# IOIO_Pump.net
KiCad netlist of a schematic drawn in EAGLE
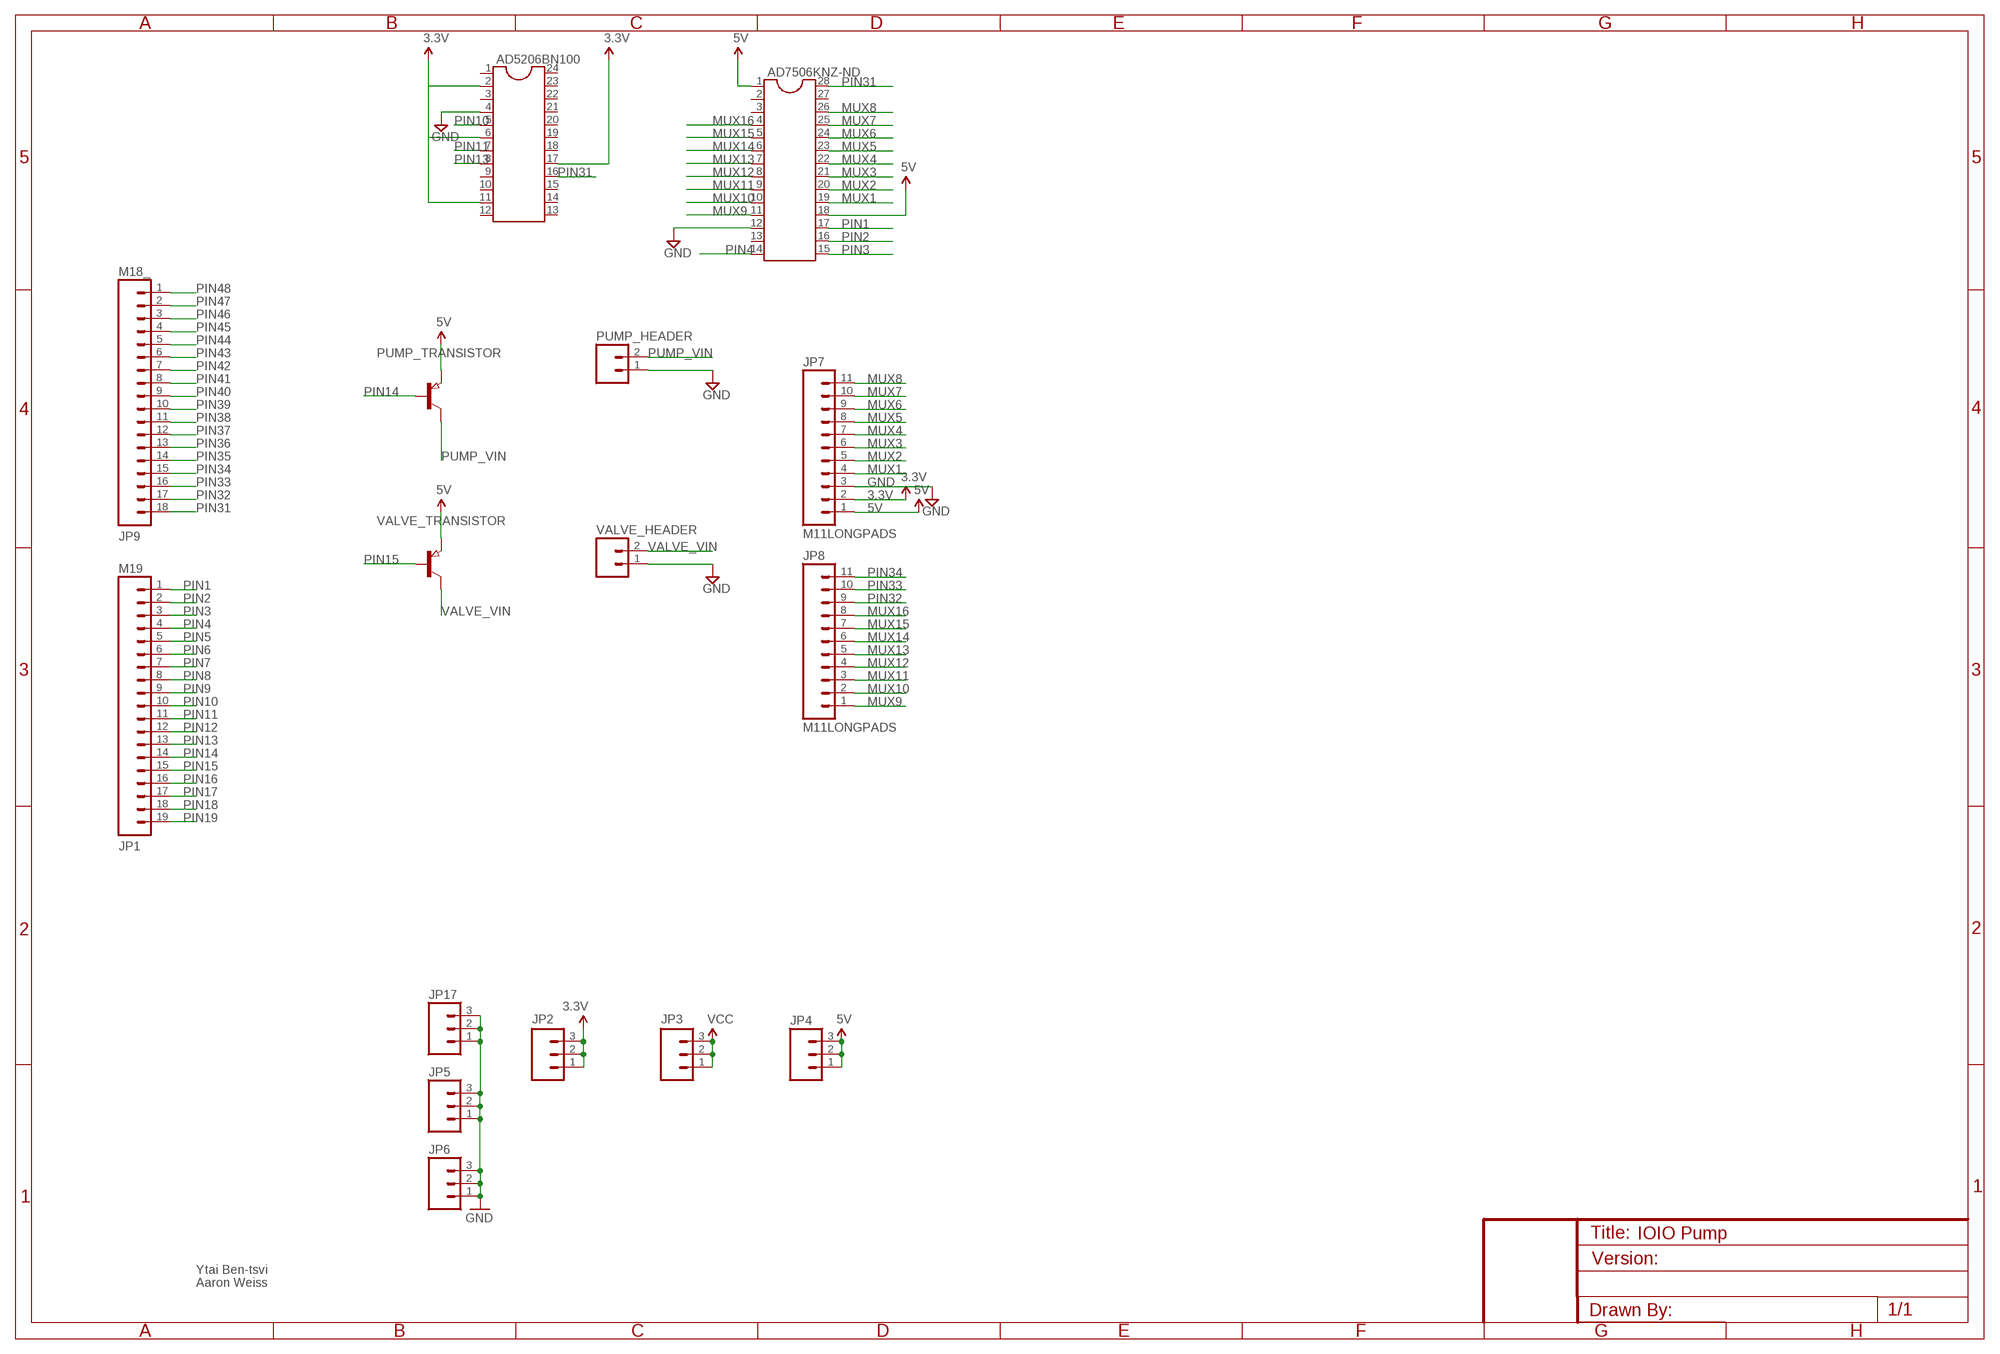
[diagram p0: schematic, sheet 1]

(export (version "E")
  (design (tool "Eeschema 10.0.6"))
  (components
    (comp (ref "AD5206BN100")
      (value "DIL24-3")
      (footprint "eagle-import:DIL24-3")
      (libsource (lib "eagle-import") (part "DIL24-3"))
    )
    (comp (ref "AD7506KNZ-ND")
      (value "DIL28")
      (footprint "eagle-import:DIL28-6")
      (libsource (lib "eagle-import") (part "DIL28"))
    )
    (comp (ref "JP1")
      (value "M19")
      (footprint "eagle-import:1X19")
      (libsource (lib "eagle-import") (part "M19"))
    )
    (comp (ref "JP2")
      (value "M03PTH")
      (footprint "eagle-import:1X03")
      (libsource (lib "eagle-import") (part "M03PTH"))
    )
    (comp (ref "JP3")
      (value "M03PTH")
      (footprint "eagle-import:1X03")
      (libsource (lib "eagle-import") (part "M03PTH"))
    )
    (comp (ref "JP4")
      (value "M03PTH")
      (footprint "eagle-import:1X03")
      (libsource (lib "eagle-import") (part "M03PTH"))
    )
    (comp (ref "JP5")
      (value "M03PTH")
      (footprint "eagle-import:1X03")
      (libsource (lib "eagle-import") (part "M03PTH"))
    )
    (comp (ref "JP6")
      (value "M03PTH")
      (footprint "eagle-import:1X03")
      (libsource (lib "eagle-import") (part "M03PTH"))
    )
    (comp (ref "JP7")
      (value "M11LONGPADS")
      (footprint "eagle-import:1X11_LONGPADS")
      (libsource (lib "eagle-import") (part "M11LONGPADS"))
    )
    (comp (ref "JP8")
      (value "M11LONGPADS")
      (footprint "eagle-import:1X11_LONGPADS")
      (libsource (lib "eagle-import") (part "M11LONGPADS"))
    )
    (comp (ref "JP9")
      (value "M18_")
      (footprint "eagle-import:1X18")
      (libsource (lib "eagle-import") (part "M18_"))
    )
    (comp (ref "JP17")
      (value "M03PTH")
      (footprint "eagle-import:1X03")
      (libsource (lib "eagle-import") (part "M03PTH"))
    )
    (comp (ref "PUMP_HEADER")
      (value "M02PTH")
      (footprint "eagle-import:1X02")
      (libsource (lib "eagle-import") (part "M02PTH"))
    )
    (comp (ref "PUMP_TRANSISTOR")
      (value "PNP-TRANSISTOR_SOT23")
      (footprint "eagle-import:SOT23")
      (libsource (lib "eagle-import") (part "PNP-TRANSISTOR_SOT23"))
    )
    (comp (ref "VALVE_HEADER")
      (value "M02PTH")
      (footprint "eagle-import:1X02")
      (libsource (lib "eagle-import") (part "M02PTH"))
    )
    (comp (ref "VALVE_TRANSISTOR")
      (value "PNP-TRANSISTOR_SOT23")
      (footprint "eagle-import:SOT23")
      (libsource (lib "eagle-import") (part "PNP-TRANSISTOR_SOT23"))
    )
  )
  (nets
    (net (code "1") (name "/MUX1") (class "Default")
      (node (ref "AD7506KNZ-ND") (pin "19") (pinfunction "19_19") (pintype "passive"))
      (node (ref "JP7") (pin "4") (pinfunction "4_4") (pintype "passive"))
    )
    (net (code "2") (name "/MUX2") (class "Default")
      (node (ref "AD7506KNZ-ND") (pin "20") (pinfunction "20_20") (pintype "passive"))
      (node (ref "JP7") (pin "5") (pinfunction "5_5") (pintype "passive"))
    )
    (net (code "3") (name "/MUX3") (class "Default")
      (node (ref "AD7506KNZ-ND") (pin "21") (pinfunction "21_21") (pintype "passive"))
      (node (ref "JP7") (pin "6") (pinfunction "6_6") (pintype "passive"))
    )
    (net (code "4") (name "/MUX4") (class "Default")
      (node (ref "AD7506KNZ-ND") (pin "22") (pinfunction "22_22") (pintype "passive"))
      (node (ref "JP7") (pin "7") (pinfunction "7_7") (pintype "passive"))
    )
    (net (code "5") (name "/MUX5") (class "Default")
      (node (ref "AD7506KNZ-ND") (pin "23") (pinfunction "23_23") (pintype "passive"))
      (node (ref "JP7") (pin "8") (pinfunction "8_8") (pintype "passive"))
    )
    (net (code "6") (name "/MUX6") (class "Default")
      (node (ref "AD7506KNZ-ND") (pin "24") (pinfunction "24_24") (pintype "passive"))
      (node (ref "JP7") (pin "9") (pinfunction "9_9") (pintype "passive"))
    )
    (net (code "7") (name "/MUX7") (class "Default")
      (node (ref "AD7506KNZ-ND") (pin "25") (pinfunction "25_25") (pintype "passive"))
      (node (ref "JP7") (pin "10") (pinfunction "10_10") (pintype "passive"))
    )
    (net (code "8") (name "/MUX8") (class "Default")
      (node (ref "AD7506KNZ-ND") (pin "26") (pinfunction "26_26") (pintype "passive"))
      (node (ref "JP7") (pin "11") (pinfunction "11_11") (pintype "passive"))
    )
    (net (code "9") (name "/MUX9") (class "Default")
      (node (ref "AD7506KNZ-ND") (pin "11") (pinfunction "11_11") (pintype "passive"))
      (node (ref "JP8") (pin "1") (pinfunction "1_1") (pintype "passive"))
    )
    (net (code "10") (name "/MUX10") (class "Default")
      (node (ref "AD7506KNZ-ND") (pin "10") (pinfunction "10_10") (pintype "passive"))
      (node (ref "JP8") (pin "2") (pinfunction "2_2") (pintype "passive"))
    )
    (net (code "11") (name "/MUX11") (class "Default")
      (node (ref "AD7506KNZ-ND") (pin "9") (pinfunction "9_9") (pintype "passive"))
      (node (ref "JP8") (pin "3") (pinfunction "3_3") (pintype "passive"))
    )
    (net (code "12") (name "/MUX12") (class "Default")
      (node (ref "AD7506KNZ-ND") (pin "8") (pinfunction "8_8") (pintype "passive"))
      (node (ref "JP8") (pin "4") (pinfunction "4_4") (pintype "passive"))
    )
    (net (code "13") (name "/MUX13") (class "Default")
      (node (ref "AD7506KNZ-ND") (pin "7") (pinfunction "7_7") (pintype "passive"))
      (node (ref "JP8") (pin "5") (pinfunction "5_5") (pintype "passive"))
    )
    (net (code "14") (name "/MUX14") (class "Default")
      (node (ref "AD7506KNZ-ND") (pin "6") (pinfunction "6_6") (pintype "passive"))
      (node (ref "JP8") (pin "6") (pinfunction "6_6") (pintype "passive"))
    )
    (net (code "15") (name "/MUX15") (class "Default")
      (node (ref "AD7506KNZ-ND") (pin "5") (pinfunction "5_5") (pintype "passive"))
      (node (ref "JP8") (pin "7") (pinfunction "7_7") (pintype "passive"))
    )
    (net (code "16") (name "/MUX16") (class "Default")
      (node (ref "AD7506KNZ-ND") (pin "4") (pinfunction "4_4") (pintype "passive"))
      (node (ref "JP8") (pin "8") (pinfunction "8_8") (pintype "passive"))
    )
    (net (code "17") (name "/PIN1") (class "Default")
      (node (ref "AD7506KNZ-ND") (pin "17") (pinfunction "17_17") (pintype "passive"))
      (node (ref "JP1") (pin "1") (pinfunction "1_1") (pintype "passive"))
    )
    (net (code "18") (name "/PIN2") (class "Default")
      (node (ref "AD7506KNZ-ND") (pin "16") (pinfunction "16_16") (pintype "passive"))
      (node (ref "JP1") (pin "2") (pinfunction "2_2") (pintype "passive"))
    )
    (net (code "19") (name "/PIN3") (class "Default")
      (node (ref "AD7506KNZ-ND") (pin "15") (pinfunction "15_15") (pintype "passive"))
      (node (ref "JP1") (pin "3") (pinfunction "3_3") (pintype "passive"))
    )
    (net (code "20") (name "/PIN4") (class "Default")
      (node (ref "AD7506KNZ-ND") (pin "14") (pinfunction "14_14") (pintype "passive"))
      (node (ref "JP1") (pin "4") (pinfunction "4_4") (pintype "passive"))
    )
    (net (code "21") (name "/PIN5") (class "Default")
      (node (ref "JP1") (pin "5") (pinfunction "5_5") (pintype "passive"))
    )
    (net (code "22") (name "/PIN6") (class "Default")
      (node (ref "JP1") (pin "6") (pinfunction "6_6") (pintype "passive"))
    )
    (net (code "23") (name "/PIN7") (class "Default")
      (node (ref "JP1") (pin "7") (pinfunction "7_7") (pintype "passive"))
    )
    (net (code "24") (name "/PIN8") (class "Default")
      (node (ref "JP1") (pin "8") (pinfunction "8_8") (pintype "passive"))
    )
    (net (code "25") (name "/PIN9") (class "Default")
      (node (ref "JP1") (pin "9") (pinfunction "9_9") (pintype "passive"))
    )
    (net (code "26") (name "/PIN10") (class "Default")
      (node (ref "AD5206BN100") (pin "5") (pinfunction "5_5") (pintype "passive"))
      (node (ref "JP1") (pin "10") (pinfunction "10_10") (pintype "passive"))
    )
    (net (code "27") (name "/PIN11") (class "Default")
      (node (ref "AD5206BN100") (pin "7") (pinfunction "7_7") (pintype "passive"))
      (node (ref "JP1") (pin "11") (pinfunction "11_11") (pintype "passive"))
    )
    (net (code "28") (name "/PIN12") (class "Default")
      (node (ref "JP1") (pin "12") (pinfunction "12_12") (pintype "passive"))
    )
    (net (code "29") (name "/PIN13") (class "Default")
      (node (ref "AD5206BN100") (pin "8") (pinfunction "8_8") (pintype "passive"))
      (node (ref "JP1") (pin "13") (pinfunction "13_13") (pintype "passive"))
    )
    (net (code "30") (name "/PIN14") (class "Default")
      (node (ref "JP1") (pin "14") (pinfunction "14_14") (pintype "passive"))
      (node (ref "PUMP_TRANSISTOR") (pin "1") (pinfunction "B_1") (pintype "passive"))
    )
    (net (code "31") (name "/PIN15") (class "Default")
      (node (ref "JP1") (pin "15") (pinfunction "15_15") (pintype "passive"))
      (node (ref "VALVE_TRANSISTOR") (pin "1") (pinfunction "B_1") (pintype "passive"))
    )
    (net (code "32") (name "/PIN16") (class "Default")
      (node (ref "JP1") (pin "16") (pinfunction "16_16") (pintype "passive"))
    )
    (net (code "33") (name "/PIN17") (class "Default")
      (node (ref "JP1") (pin "17") (pinfunction "17_17") (pintype "passive"))
    )
    (net (code "34") (name "/PIN18") (class "Default")
      (node (ref "JP1") (pin "18") (pinfunction "18_18") (pintype "passive"))
    )
    (net (code "35") (name "/PIN19") (class "Default")
      (node (ref "JP1") (pin "19") (pinfunction "19_19") (pintype "passive"))
    )
    (net (code "36") (name "/PIN31") (class "Default")
      (node (ref "AD5206BN100") (pin "16") (pinfunction "16_16") (pintype "passive"))
      (node (ref "AD7506KNZ-ND") (pin "28") (pinfunction "28_28") (pintype "passive"))
      (node (ref "JP9") (pin "18") (pinfunction "18_18") (pintype "passive"))
    )
    (net (code "37") (name "/PIN32") (class "Default")
      (node (ref "JP8") (pin "9") (pinfunction "9_9") (pintype "passive"))
      (node (ref "JP9") (pin "17") (pinfunction "17_17") (pintype "passive"))
    )
    (net (code "38") (name "/PIN33") (class "Default")
      (node (ref "JP8") (pin "10") (pinfunction "10_10") (pintype "passive"))
      (node (ref "JP9") (pin "16") (pinfunction "16_16") (pintype "passive"))
    )
    (net (code "39") (name "/PIN34") (class "Default")
      (node (ref "JP8") (pin "11") (pinfunction "11_11") (pintype "passive"))
      (node (ref "JP9") (pin "15") (pinfunction "15_15") (pintype "passive"))
    )
    (net (code "40") (name "/PIN35") (class "Default")
      (node (ref "JP9") (pin "14") (pinfunction "14_14") (pintype "passive"))
    )
    (net (code "41") (name "/PIN36") (class "Default")
      (node (ref "JP9") (pin "13") (pinfunction "13_13") (pintype "passive"))
    )
    (net (code "42") (name "/PIN37") (class "Default")
      (node (ref "JP9") (pin "12") (pinfunction "12_12") (pintype "passive"))
    )
    (net (code "43") (name "/PIN38") (class "Default")
      (node (ref "JP9") (pin "11") (pinfunction "11_11") (pintype "passive"))
    )
    (net (code "44") (name "/PIN39") (class "Default")
      (node (ref "JP9") (pin "10") (pinfunction "10_10") (pintype "passive"))
    )
    (net (code "45") (name "/PIN40") (class "Default")
      (node (ref "JP9") (pin "9") (pinfunction "9_9") (pintype "passive"))
    )
    (net (code "46") (name "/PIN41") (class "Default")
      (node (ref "JP9") (pin "8") (pinfunction "8_8") (pintype "passive"))
    )
    (net (code "47") (name "/PIN42") (class "Default")
      (node (ref "JP9") (pin "7") (pinfunction "7_7") (pintype "passive"))
    )
    (net (code "48") (name "/PIN43") (class "Default")
      (node (ref "JP9") (pin "6") (pinfunction "6_6") (pintype "passive"))
    )
    (net (code "49") (name "/PIN44") (class "Default")
      (node (ref "JP9") (pin "5") (pinfunction "5_5") (pintype "passive"))
    )
    (net (code "50") (name "/PIN45") (class "Default")
      (node (ref "JP9") (pin "4") (pinfunction "4_4") (pintype "passive"))
    )
    (net (code "51") (name "/PIN46") (class "Default")
      (node (ref "JP9") (pin "3") (pinfunction "3_3") (pintype "passive"))
    )
    (net (code "52") (name "/PIN47") (class "Default")
      (node (ref "JP9") (pin "2") (pinfunction "2_2") (pintype "passive"))
    )
    (net (code "53") (name "/PIN48") (class "Default")
      (node (ref "JP9") (pin "1") (pinfunction "1_1") (pintype "passive"))
    )
    (net (code "54") (name "/PUMP_VIN") (class "Default")
      (node (ref "PUMP_HEADER") (pin "2") (pinfunction "2_2") (pintype "passive"))
      (node (ref "PUMP_TRANSISTOR") (pin "3") (pinfunction "C_3") (pintype "passive"))
    )
    (net (code "55") (name "/VALVE_VIN") (class "Default")
      (node (ref "VALVE_HEADER") (pin "2") (pinfunction "2_2") (pintype "passive"))
      (node (ref "VALVE_TRANSISTOR") (pin "3") (pinfunction "C_3") (pintype "passive"))
    )
    (net (code "56") (name "3.3V") (class "Default")
      (node (ref "AD5206BN100") (pin "11") (pinfunction "11_11") (pintype "passive"))
      (node (ref "AD5206BN100") (pin "17") (pinfunction "17_17") (pintype "passive"))
      (node (ref "AD5206BN100") (pin "2") (pinfunction "2_2") (pintype "passive"))
      (node (ref "AD5206BN100") (pin "6") (pinfunction "6_6") (pintype "passive"))
      (node (ref "JP2") (pin "1") (pinfunction "1_1") (pintype "passive"))
      (node (ref "JP2") (pin "2") (pinfunction "2_2") (pintype "passive"))
      (node (ref "JP2") (pin "3") (pinfunction "3_3") (pintype "passive"))
      (node (ref "JP7") (pin "2") (pinfunction "2_2") (pintype "passive"))
    )
    (net (code "57") (name "5V") (class "Default")
      (node (ref "AD7506KNZ-ND") (pin "1") (pinfunction "1_1") (pintype "passive"))
      (node (ref "AD7506KNZ-ND") (pin "18") (pinfunction "18_18") (pintype "passive"))
      (node (ref "JP4") (pin "1") (pinfunction "1_1") (pintype "passive"))
      (node (ref "JP4") (pin "2") (pinfunction "2_2") (pintype "passive"))
      (node (ref "JP4") (pin "3") (pinfunction "3_3") (pintype "passive"))
      (node (ref "JP7") (pin "1") (pinfunction "1_1") (pintype "passive"))
      (node (ref "PUMP_TRANSISTOR") (pin "2") (pinfunction "E_2") (pintype "passive"))
      (node (ref "VALVE_TRANSISTOR") (pin "2") (pinfunction "E_2") (pintype "passive"))
    )
    (net (code "58") (name "GND") (class "Default")
      (node (ref "AD5206BN100") (pin "4") (pinfunction "4_4") (pintype "passive"))
      (node (ref "AD7506KNZ-ND") (pin "12") (pinfunction "12_12") (pintype "passive"))
      (node (ref "JP17") (pin "1") (pinfunction "1_1") (pintype "passive"))
      (node (ref "JP17") (pin "2") (pinfunction "2_2") (pintype "passive"))
      (node (ref "JP17") (pin "3") (pinfunction "3_3") (pintype "passive"))
      (node (ref "JP5") (pin "1") (pinfunction "1_1") (pintype "passive"))
      (node (ref "JP5") (pin "2") (pinfunction "2_2") (pintype "passive"))
      (node (ref "JP5") (pin "3") (pinfunction "3_3") (pintype "passive"))
      (node (ref "JP6") (pin "1") (pinfunction "1_1") (pintype "passive"))
      (node (ref "JP6") (pin "2") (pinfunction "2_2") (pintype "passive"))
      (node (ref "JP6") (pin "3") (pinfunction "3_3") (pintype "passive"))
      (node (ref "JP7") (pin "3") (pinfunction "3_3") (pintype "passive"))
      (node (ref "PUMP_HEADER") (pin "1") (pinfunction "1_1") (pintype "passive"))
      (node (ref "VALVE_HEADER") (pin "1") (pinfunction "1_1") (pintype "passive"))
    )
    (net (code "59") (name "VCC") (class "Default")
      (node (ref "JP3") (pin "1") (pinfunction "1_1") (pintype "passive"))
      (node (ref "JP3") (pin "2") (pinfunction "2_2") (pintype "passive"))
      (node (ref "JP3") (pin "3") (pinfunction "3_3") (pintype "passive"))
    )
    (net (code "60") (name "unconnected-(AD5206BN100-Pad1)") (class "Default")
      (node (ref "AD5206BN100") (pin "1") (pinfunction "1_1") (pintype "passive"))
    )
    (net (code "61") (name "unconnected-(AD5206BN100-Pad3)") (class "Default")
      (node (ref "AD5206BN100") (pin "3") (pinfunction "3_3") (pintype "passive"))
    )
    (net (code "62") (name "unconnected-(AD5206BN100-Pad9)") (class "Default")
      (node (ref "AD5206BN100") (pin "9") (pinfunction "9_9") (pintype "passive"))
    )
    (net (code "63") (name "unconnected-(AD5206BN100-Pad10)") (class "Default")
      (node (ref "AD5206BN100") (pin "10") (pinfunction "10_10") (pintype "passive"))
    )
    (net (code "64") (name "unconnected-(AD5206BN100-Pad12)") (class "Default")
      (node (ref "AD5206BN100") (pin "12") (pinfunction "12_12") (pintype "passive"))
    )
    (net (code "65") (name "unconnected-(AD5206BN100-Pad13)") (class "Default")
      (node (ref "AD5206BN100") (pin "13") (pinfunction "13_13") (pintype "passive"))
    )
    (net (code "66") (name "unconnected-(AD5206BN100-Pad14)") (class "Default")
      (node (ref "AD5206BN100") (pin "14") (pinfunction "14_14") (pintype "passive"))
    )
    (net (code "67") (name "unconnected-(AD5206BN100-Pad15)") (class "Default")
      (node (ref "AD5206BN100") (pin "15") (pinfunction "15_15") (pintype "passive"))
    )
    (net (code "68") (name "unconnected-(AD5206BN100-Pad18)") (class "Default")
      (node (ref "AD5206BN100") (pin "18") (pinfunction "18_18") (pintype "passive"))
    )
    (net (code "69") (name "unconnected-(AD5206BN100-Pad19)") (class "Default")
      (node (ref "AD5206BN100") (pin "19") (pinfunction "19_19") (pintype "passive"))
    )
    (net (code "70") (name "unconnected-(AD5206BN100-Pad20)") (class "Default")
      (node (ref "AD5206BN100") (pin "20") (pinfunction "20_20") (pintype "passive"))
    )
    (net (code "71") (name "unconnected-(AD5206BN100-Pad21)") (class "Default")
      (node (ref "AD5206BN100") (pin "21") (pinfunction "21_21") (pintype "passive"))
    )
    (net (code "72") (name "unconnected-(AD5206BN100-Pad22)") (class "Default")
      (node (ref "AD5206BN100") (pin "22") (pinfunction "22_22") (pintype "passive"))
    )
    (net (code "73") (name "unconnected-(AD5206BN100-Pad23)") (class "Default")
      (node (ref "AD5206BN100") (pin "23") (pinfunction "23_23") (pintype "passive"))
    )
    (net (code "74") (name "unconnected-(AD5206BN100-Pad24)") (class "Default")
      (node (ref "AD5206BN100") (pin "24") (pinfunction "24_24") (pintype "passive"))
    )
    (net (code "75") (name "unconnected-(AD7506KNZ-ND-Pad2)") (class "Default")
      (node (ref "AD7506KNZ-ND") (pin "2") (pinfunction "2_2") (pintype "passive"))
    )
    (net (code "76") (name "unconnected-(AD7506KNZ-ND-Pad3)") (class "Default")
      (node (ref "AD7506KNZ-ND") (pin "3") (pinfunction "3_3") (pintype "passive"))
    )
    (net (code "77") (name "unconnected-(AD7506KNZ-ND-Pad13)") (class "Default")
      (node (ref "AD7506KNZ-ND") (pin "13") (pinfunction "13_13") (pintype "passive"))
    )
    (net (code "78") (name "unconnected-(AD7506KNZ-ND-Pad27)") (class "Default")
      (node (ref "AD7506KNZ-ND") (pin "27") (pinfunction "27_27") (pintype "passive"))
    )
  )
)
